# ALU_ZF.net
KiCad netlist of a schematic drawn in Altium Designer
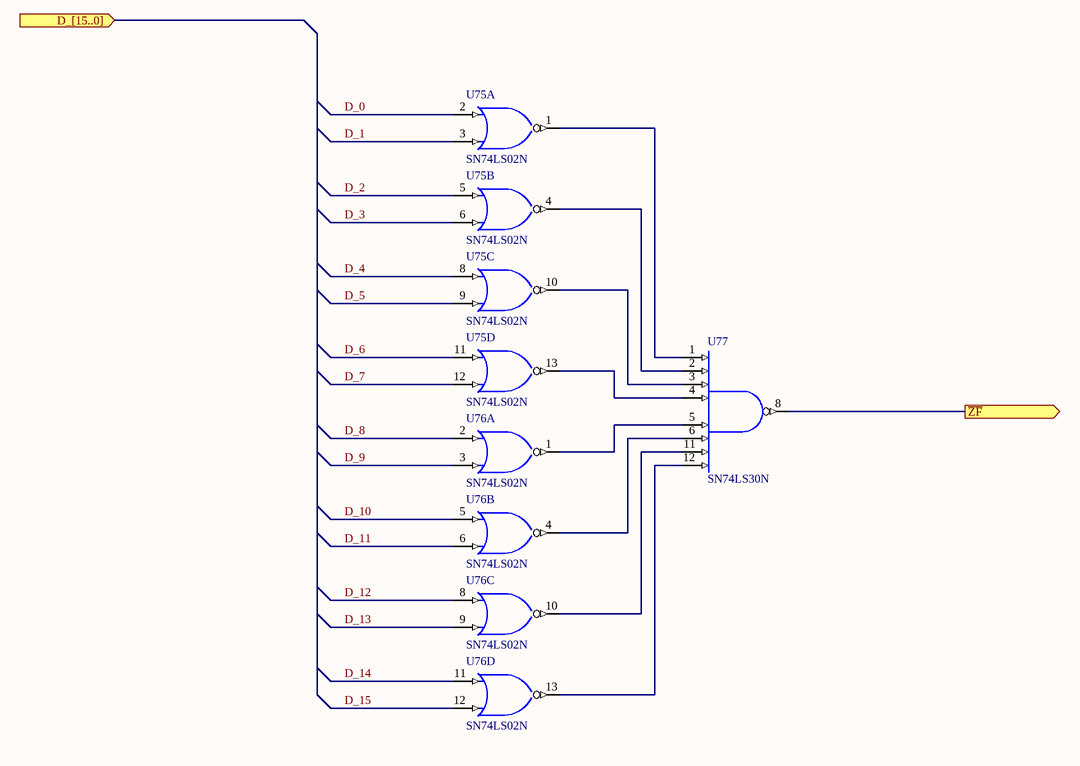
[diagram p0: ALU_ZF.SchDoc]

(export (version "E")
  (design (tool "Eeschema 10.0.6"))
  (components
    (comp (ref "U75")
      (value "SN74LS02N")
      (footprint "N014")
      (description "Quadruple 2-Input Positive-NOR Gate")
      (fields (field (name "PUBLISHER") "Altium Limited"))
      (libsource (lib "TI Logic Gate 2") (part "SN74LS02N"))
    )
    (comp (ref "U76")
      (value "SN74LS02N")
      (footprint "N014")
      (description "Quadruple 2-Input Positive-NOR Gate")
      (fields (field (name "PUBLISHER") "Altium Limited"))
      (libsource (lib "TI Logic Gate 2") (part "SN74LS02N"))
    )
    (comp (ref "U77")
      (value "SN74LS30N")
      (footprint "N014")
      (description "8-Input Positive-NAND Gate")
      (fields (field (name "PUBLISHER") "Altium Limited"))
      (libsource (lib "TI Logic Gate 2") (part "SN74LS30N"))
    )
  )
  (nets
    (net (code "1") (name "/D_0") (class "Default")
      (node (ref "U75") (pin "2") (pinfunction "A_2") (pintype "input"))
    )
    (net (code "2") (name "/D_1") (class "Default")
      (node (ref "U75") (pin "3") (pinfunction "B_3") (pintype "input"))
    )
    (net (code "3") (name "/D_2") (class "Default")
      (node (ref "U75") (pin "5") (pinfunction "A_5") (pintype "input"))
    )
    (net (code "4") (name "/D_3") (class "Default")
      (node (ref "U75") (pin "6") (pinfunction "B_6") (pintype "input"))
    )
    (net (code "5") (name "/D_4") (class "Default")
      (node (ref "U75") (pin "8") (pinfunction "A_8") (pintype "input"))
    )
    (net (code "6") (name "/D_5") (class "Default")
      (node (ref "U75") (pin "9") (pinfunction "B_9") (pintype "input"))
    )
    (net (code "7") (name "/D_6") (class "Default")
      (node (ref "U75") (pin "11") (pinfunction "A_11") (pintype "input"))
    )
    (net (code "8") (name "/D_7") (class "Default")
      (node (ref "U75") (pin "12") (pinfunction "B_12") (pintype "input"))
    )
    (net (code "9") (name "/D_8") (class "Default")
      (node (ref "U76") (pin "2") (pinfunction "A_2") (pintype "input"))
    )
    (net (code "10") (name "/D_9") (class "Default")
      (node (ref "U76") (pin "3") (pinfunction "B_3") (pintype "input"))
    )
    (net (code "11") (name "/D_10") (class "Default")
      (node (ref "U76") (pin "5") (pinfunction "A_5") (pintype "input"))
    )
    (net (code "12") (name "/D_11") (class "Default")
      (node (ref "U76") (pin "6") (pinfunction "B_6") (pintype "input"))
    )
    (net (code "13") (name "/D_12") (class "Default")
      (node (ref "U76") (pin "8") (pinfunction "A_8") (pintype "input"))
    )
    (net (code "14") (name "/D_13") (class "Default")
      (node (ref "U76") (pin "9") (pinfunction "B_9") (pintype "input"))
    )
    (net (code "15") (name "/D_14") (class "Default")
      (node (ref "U76") (pin "11") (pinfunction "A_11") (pintype "input"))
    )
    (net (code "16") (name "/D_15") (class "Default")
      (node (ref "U76") (pin "12") (pinfunction "B_12") (pintype "input"))
    )
    (net (code "18") (name "/~{ZF}") (class "Default")
      (node (ref "U77") (pin "8") (pinfunction "Y_8") (pintype "output"))
    )
    (net (code "19") (name "GND") (class "Default")
      (node (ref "U75") (pin "7") (pinfunction "GND_7") (pintype "power_in"))
      (node (ref "U76") (pin "7") (pinfunction "GND_7") (pintype "power_in"))
      (node (ref "U77") (pin "7") (pinfunction "GND_7") (pintype "power_in"))
    )
    (net (code "20") (name "Net-(U75A-Y)") (class "Default")
      (node (ref "U75") (pin "1") (pinfunction "Y_1") (pintype "output"))
      (node (ref "U77") (pin "1") (pinfunction "A_1") (pintype "input"))
    )
    (net (code "21") (name "Net-(U75B-Y)") (class "Default")
      (node (ref "U75") (pin "4") (pinfunction "Y_4") (pintype "output"))
      (node (ref "U77") (pin "2") (pinfunction "B_2") (pintype "input"))
    )
    (net (code "22") (name "Net-(U75C-Y)") (class "Default")
      (node (ref "U75") (pin "10") (pinfunction "Y_10") (pintype "output"))
      (node (ref "U77") (pin "3") (pinfunction "C_3") (pintype "input"))
    )
    (net (code "23") (name "Net-(U75D-Y)") (class "Default")
      (node (ref "U75") (pin "13") (pinfunction "Y_13") (pintype "output"))
      (node (ref "U77") (pin "4") (pinfunction "D_4") (pintype "input"))
    )
    (net (code "24") (name "Net-(U76A-Y)") (class "Default")
      (node (ref "U76") (pin "1") (pinfunction "Y_1") (pintype "output"))
      (node (ref "U77") (pin "5") (pinfunction "E_5") (pintype "input"))
    )
    (net (code "25") (name "Net-(U76B-Y)") (class "Default")
      (node (ref "U76") (pin "4") (pinfunction "Y_4") (pintype "output"))
      (node (ref "U77") (pin "6") (pinfunction "F_6") (pintype "input"))
    )
    (net (code "26") (name "Net-(U76C-Y)") (class "Default")
      (node (ref "U76") (pin "10") (pinfunction "Y_10") (pintype "output"))
      (node (ref "U77") (pin "11") (pinfunction "G_11") (pintype "input"))
    )
    (net (code "27") (name "Net-(U76D-Y)") (class "Default")
      (node (ref "U76") (pin "13") (pinfunction "Y_13") (pintype "output"))
      (node (ref "U77") (pin "12") (pinfunction "H_12") (pintype "input"))
    )
    (net (code "28") (name "VCC") (class "Default")
      (node (ref "U75") (pin "14") (pinfunction "VCC_14") (pintype "power_in"))
      (node (ref "U76") (pin "14") (pinfunction "VCC_14") (pintype "power_in"))
      (node (ref "U77") (pin "14") (pinfunction "VCC_14") (pintype "power_in"))
    )
  )
)
